# DDR3_2.net
KiCad netlist of a schematic drawn in Altium Designer
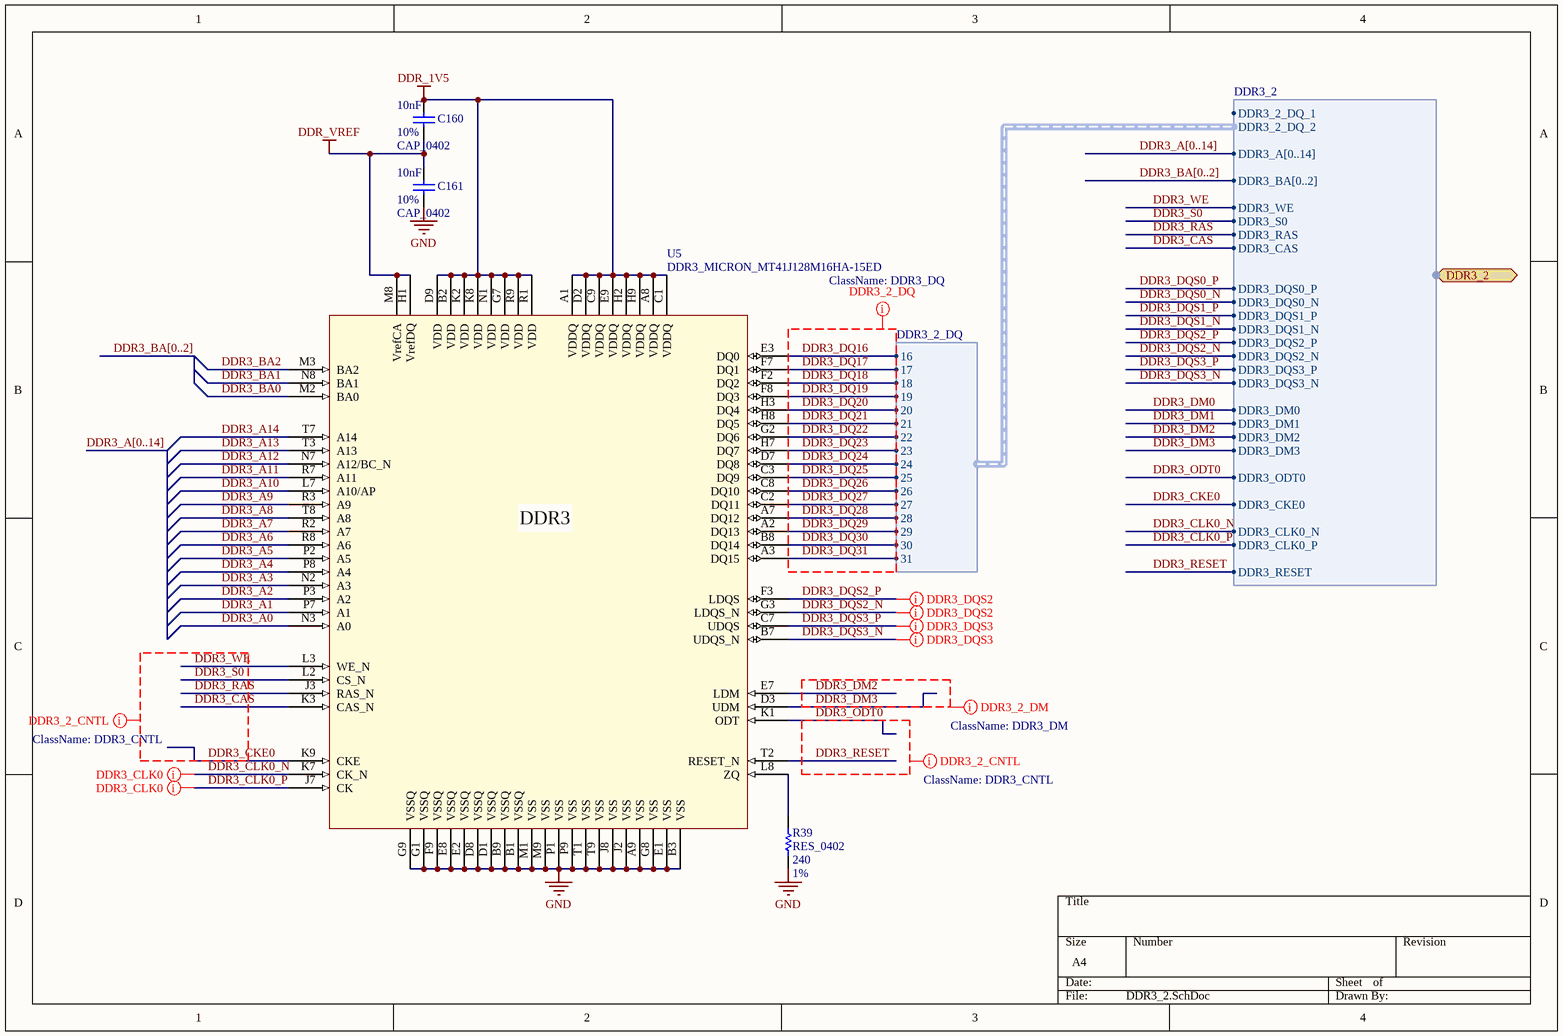
[diagram p0: DDR3_2.SchDoc]

(export (version "E")
  (design (tool "Eeschema 10.0.6"))
  (components
    (comp (ref "C160")
      (value "CAP_0402")
      (footprint "CAPC0402(1005)60_N:CAPC0402(1005)60_N")
      (description "10000pF, ceramic, 10% 6.3V X5R, 0402")
      (fields
        (field (name "ALTIUM_VALUE") "10nF")
        (field (name "TOLERANCE") "10%")
        (field (name "PART NUMBER") "GRM155R60J103KA01D")
        (field (name "MANUFACTURER") "Murata Electronics North America")
      )
      (libsource (lib "COMRAD_Database") (part "CAP_0402"))
    )
    (comp (ref "C161")
      (value "CAP_0402")
      (footprint "CAPC0402(1005)60_N:CAPC0402(1005)60_N")
      (description "10000pF, ceramic, 10% 6.3V X5R, 0402")
      (fields
        (field (name "ALTIUM_VALUE") "10nF")
        (field (name "TOLERANCE") "10%")
        (field (name "PART NUMBER") "GRM155R60J103KA01D")
        (field (name "MANUFACTURER") "Murata Electronics North America")
      )
      (libsource (lib "COMRAD_Database") (part "CAP_0402"))
    )
    (comp (ref "R39")
      (value "RES_0402")
      (footprint "RESC0402(1005)_N:RESC0402(1005)_N")
      (description "240 ohm, 1% 1/16W, 0402")
      (fields
        (field (name "ALTIUM_VALUE") "240")
        (field (name "TOLERANCE") "1%")
        (field (name "PART NUMBER") "CRCW0402240RFKED")
        (field (name "MANUFACTURER") "Vishay/Dale")
      )
      (libsource (lib "COMRAD_Database") (part "RES_0402"))
    )
    (comp (ref "U5")
      (value "DDR3_MICRON_MT41J128M16HA-15ED")
      (footprint "DDR3_MICRON_MT41J128M16HA-15ED_FBGA96")
      (description "MT41J128M16HA-15E:D, DDR3 SDRAM 4Gb x4, x8, x16, FBGA96")
      (fields (field (name "PART NUMBER") "MT41J128M16HA-15E:D TR") (field (name "MANUFACTURER") "MICRON"))
      (libsource (lib "COMRAD_Database") (part "DDR3_MICRON_MT41J128M16HA-15ED"))
    )
  )
  (nets
    (net (code "4") (name "/DDR3_A0") (class "Default")
      (node (ref "U5") (pin "N3") (pinfunction "A0_N3") (pintype "input"))
    )
    (net (code "5") (name "/DDR3_A1") (class "Default")
      (node (ref "U5") (pin "P7") (pinfunction "A1_P7") (pintype "input"))
    )
    (net (code "6") (name "/DDR3_A2") (class "Default")
      (node (ref "U5") (pin "P3") (pinfunction "A2_P3") (pintype "input"))
    )
    (net (code "7") (name "/DDR3_A3") (class "Default")
      (node (ref "U5") (pin "N2") (pinfunction "A3_N2") (pintype "input"))
    )
    (net (code "8") (name "/DDR3_A4") (class "Default")
      (node (ref "U5") (pin "P8") (pinfunction "A4_P8") (pintype "input"))
    )
    (net (code "9") (name "/DDR3_A5") (class "Default")
      (node (ref "U5") (pin "P2") (pinfunction "A5_P2") (pintype "input"))
    )
    (net (code "10") (name "/DDR3_A6") (class "Default")
      (node (ref "U5") (pin "R8") (pinfunction "A6_R8") (pintype "input"))
    )
    (net (code "11") (name "/DDR3_A7") (class "Default")
      (node (ref "U5") (pin "R2") (pinfunction "A7_R2") (pintype "input"))
    )
    (net (code "12") (name "/DDR3_A8") (class "Default")
      (node (ref "U5") (pin "T8") (pinfunction "A8_T8") (pintype "input"))
    )
    (net (code "13") (name "/DDR3_A9") (class "Default")
      (node (ref "U5") (pin "R3") (pinfunction "A9_R3") (pintype "input"))
    )
    (net (code "14") (name "/DDR3_A10") (class "Default")
      (node (ref "U5") (pin "L7") (pinfunction "A10/AP_L7") (pintype "input"))
    )
    (net (code "15") (name "/DDR3_A11") (class "Default")
      (node (ref "U5") (pin "R7") (pinfunction "A11_R7") (pintype "input"))
    )
    (net (code "16") (name "/DDR3_A12") (class "Default")
      (node (ref "U5") (pin "N7") (pinfunction "A12/BC_N_N7") (pintype "input"))
    )
    (net (code "17") (name "/DDR3_A13") (class "Default")
      (node (ref "U5") (pin "T3") (pinfunction "A13_T3") (pintype "input"))
    )
    (net (code "18") (name "/DDR3_A14") (class "Default")
      (node (ref "U5") (pin "T7") (pinfunction "A14_T7") (pintype "input"))
    )
    (net (code "20") (name "/DDR3_BA0") (class "Default")
      (node (ref "U5") (pin "M2") (pinfunction "BA0_M2") (pintype "input"))
    )
    (net (code "21") (name "/DDR3_BA1") (class "Default")
      (node (ref "U5") (pin "N8") (pinfunction "BA1_N8") (pintype "input"))
    )
    (net (code "22") (name "/DDR3_BA2") (class "Default")
      (node (ref "U5") (pin "M3") (pinfunction "BA2_M3") (pintype "input"))
    )
    (net (code "24") (name "/DDR3_CAS") (class "Default")
      (node (ref "U5") (pin "K3") (pinfunction "CAS_N_K3") (pintype "input"))
    )
    (net (code "25") (name "/DDR3_CKE0") (class "Default")
      (node (ref "U5") (pin "K9") (pinfunction "CKE_K9") (pintype "input"))
    )
    (net (code "26") (name "/DDR3_CLK0_N") (class "Default")
      (node (ref "U5") (pin "K7") (pinfunction "CK_N_K7") (pintype "input"))
    )
    (net (code "27") (name "/DDR3_CLK0_P") (class "Default")
      (node (ref "U5") (pin "J7") (pinfunction "CK_J7") (pintype "input"))
    )
    (net (code "30") (name "/DDR3_DM2") (class "Default")
      (node (ref "U5") (pin "E7") (pinfunction "LDM_E7") (pintype "input"))
    )
    (net (code "31") (name "/DDR3_DM3") (class "Default")
      (node (ref "U5") (pin "D3") (pinfunction "UDM_D3") (pintype "input"))
    )
    (net (code "32") (name "/DDR3_DQ16") (class "Default")
      (node (ref "U5") (pin "E3") (pinfunction "DQ0_E3") (pintype "bidirectional"))
    )
    (net (code "33") (name "/DDR3_DQ17") (class "Default")
      (node (ref "U5") (pin "F7") (pinfunction "DQ1_F7") (pintype "bidirectional"))
    )
    (net (code "34") (name "/DDR3_DQ18") (class "Default")
      (node (ref "U5") (pin "F2") (pinfunction "DQ2_F2") (pintype "bidirectional"))
    )
    (net (code "35") (name "/DDR3_DQ19") (class "Default")
      (node (ref "U5") (pin "F8") (pinfunction "DQ3_F8") (pintype "bidirectional"))
    )
    (net (code "36") (name "/DDR3_DQ20") (class "Default")
      (node (ref "U5") (pin "H3") (pinfunction "DQ4_H3") (pintype "bidirectional"))
    )
    (net (code "37") (name "/DDR3_DQ21") (class "Default")
      (node (ref "U5") (pin "H8") (pinfunction "DQ5_H8") (pintype "bidirectional"))
    )
    (net (code "38") (name "/DDR3_DQ22") (class "Default")
      (node (ref "U5") (pin "G2") (pinfunction "DQ6_G2") (pintype "bidirectional"))
    )
    (net (code "39") (name "/DDR3_DQ23") (class "Default")
      (node (ref "U5") (pin "H7") (pinfunction "DQ7_H7") (pintype "bidirectional"))
    )
    (net (code "40") (name "/DDR3_DQ24") (class "Default")
      (node (ref "U5") (pin "D7") (pinfunction "DQ8_D7") (pintype "bidirectional"))
    )
    (net (code "41") (name "/DDR3_DQ25") (class "Default")
      (node (ref "U5") (pin "C3") (pinfunction "DQ9_C3") (pintype "bidirectional"))
    )
    (net (code "42") (name "/DDR3_DQ26") (class "Default")
      (node (ref "U5") (pin "C8") (pinfunction "DQ10_C8") (pintype "bidirectional"))
    )
    (net (code "43") (name "/DDR3_DQ27") (class "Default")
      (node (ref "U5") (pin "C2") (pinfunction "DQ11_C2") (pintype "bidirectional"))
    )
    (net (code "44") (name "/DDR3_DQ28") (class "Default")
      (node (ref "U5") (pin "A7") (pinfunction "DQ12_A7") (pintype "bidirectional"))
    )
    (net (code "45") (name "/DDR3_DQ29") (class "Default")
      (node (ref "U5") (pin "A2") (pinfunction "DQ13_A2") (pintype "bidirectional"))
    )
    (net (code "46") (name "/DDR3_DQ30") (class "Default")
      (node (ref "U5") (pin "B8") (pinfunction "DQ14_B8") (pintype "bidirectional"))
    )
    (net (code "47") (name "/DDR3_DQ31") (class "Default")
      (node (ref "U5") (pin "A3") (pinfunction "DQ15_A3") (pintype "bidirectional"))
    )
    (net (code "52") (name "/DDR3_DQS2_N") (class "Default")
      (node (ref "U5") (pin "G3") (pinfunction "LDQS_N_G3") (pintype "bidirectional"))
    )
    (net (code "53") (name "/DDR3_DQS2_P") (class "Default")
      (node (ref "U5") (pin "F3") (pinfunction "LDQS_F3") (pintype "bidirectional"))
    )
    (net (code "54") (name "/DDR3_DQS3_N") (class "Default")
      (node (ref "U5") (pin "B7") (pinfunction "UDQS_N_B7") (pintype "bidirectional"))
    )
    (net (code "55") (name "/DDR3_DQS3_P") (class "Default")
      (node (ref "U5") (pin "C7") (pinfunction "UDQS_C7") (pintype "bidirectional"))
    )
    (net (code "56") (name "/DDR3_ODT0") (class "Default")
      (node (ref "U5") (pin "K1") (pinfunction "ODT_K1") (pintype "input"))
    )
    (net (code "57") (name "/DDR3_RAS") (class "Default")
      (node (ref "U5") (pin "J3") (pinfunction "RAS_N_J3") (pintype "input"))
    )
    (net (code "58") (name "/DDR3_RESET") (class "Default")
      (node (ref "U5") (pin "T2") (pinfunction "RESET_N_T2") (pintype "input"))
    )
    (net (code "59") (name "/DDR3_S0") (class "Default")
      (node (ref "U5") (pin "L2") (pinfunction "CS_N_L2") (pintype "input"))
    )
    (net (code "60") (name "/DDR3_WE") (class "Default")
      (node (ref "U5") (pin "L3") (pinfunction "WE_N_L3") (pintype "input"))
    )
    (net (code "63") (name "DDR_1V5") (class "Default")
      (node (ref "C160") (pin "2") (pinfunction "2_2") (pintype "passive"))
      (node (ref "U5") (pin "A1") (pinfunction "VDDQ_A1") (pintype "power_in"))
      (node (ref "U5") (pin "A8") (pinfunction "VDDQ_A8") (pintype "power_in"))
      (node (ref "U5") (pin "B2") (pinfunction "VDD_B2") (pintype "power_in"))
      (node (ref "U5") (pin "C1") (pinfunction "VDDQ_C1") (pintype "power_in"))
      (node (ref "U5") (pin "C9") (pinfunction "VDDQ_C9") (pintype "power_in"))
      (node (ref "U5") (pin "D2") (pinfunction "VDDQ_D2") (pintype "power_in"))
      (node (ref "U5") (pin "D9") (pinfunction "VDD_D9") (pintype "power_in"))
      (node (ref "U5") (pin "E9") (pinfunction "VDDQ_E9") (pintype "power_in"))
      (node (ref "U5") (pin "G7") (pinfunction "VDD_G7") (pintype "power_in"))
      (node (ref "U5") (pin "H2") (pinfunction "VDDQ_H2") (pintype "power_in"))
      (node (ref "U5") (pin "H9") (pinfunction "VDDQ_H9") (pintype "power_in"))
      (node (ref "U5") (pin "K2") (pinfunction "VDD_K2") (pintype "power_in"))
      (node (ref "U5") (pin "K8") (pinfunction "VDD_K8") (pintype "power_in"))
      (node (ref "U5") (pin "N1") (pinfunction "VDD_N1") (pintype "power_in"))
      (node (ref "U5") (pin "R1") (pinfunction "VDD_R1") (pintype "power_in"))
      (node (ref "U5") (pin "R9") (pinfunction "VDD_R9") (pintype "power_in"))
    )
    (net (code "64") (name "DDR_VREF") (class "Default")
      (node (ref "C160") (pin "1") (pinfunction "1_1") (pintype "passive"))
      (node (ref "C161") (pin "2") (pinfunction "2_2") (pintype "passive"))
      (node (ref "U5") (pin "H1") (pinfunction "VrefDQ_H1") (pintype "power_in"))
      (node (ref "U5") (pin "M8") (pinfunction "VrefCA_M8") (pintype "power_in"))
    )
    (net (code "65") (name "GND") (class "Default")
      (node (ref "C161") (pin "1") (pinfunction "1_1") (pintype "passive"))
      (node (ref "R39") (pin "1") (pinfunction "1_1") (pintype "passive"))
      (node (ref "U5") (pin "A9") (pinfunction "VSS_A9") (pintype "power_in"))
      (node (ref "U5") (pin "B1") (pinfunction "VSSQ_B1") (pintype "power_in"))
      (node (ref "U5") (pin "B3") (pinfunction "VSS_B3") (pintype "power_in"))
      (node (ref "U5") (pin "B9") (pinfunction "VSSQ_B9") (pintype "power_in"))
      (node (ref "U5") (pin "D1") (pinfunction "VSSQ_D1") (pintype "power_in"))
      (node (ref "U5") (pin "D8") (pinfunction "VSSQ_D8") (pintype "power_in"))
      (node (ref "U5") (pin "E1") (pinfunction "VSS_E1") (pintype "power_in"))
      (node (ref "U5") (pin "E2") (pinfunction "VSSQ_E2") (pintype "power_in"))
      (node (ref "U5") (pin "E8") (pinfunction "VSSQ_E8") (pintype "power_in"))
      (node (ref "U5") (pin "F9") (pinfunction "VSSQ_F9") (pintype "power_in"))
      (node (ref "U5") (pin "G1") (pinfunction "VSSQ_G1") (pintype "power_in"))
      (node (ref "U5") (pin "G8") (pinfunction "VSS_G8") (pintype "power_in"))
      (node (ref "U5") (pin "G9") (pinfunction "VSSQ_G9") (pintype "power_in"))
      (node (ref "U5") (pin "J2") (pinfunction "VSS_J2") (pintype "power_in"))
      (node (ref "U5") (pin "J8") (pinfunction "VSS_J8") (pintype "power_in"))
      (node (ref "U5") (pin "M1") (pinfunction "VSS_M1") (pintype "power_in"))
      (node (ref "U5") (pin "M9") (pinfunction "VSS_M9") (pintype "power_in"))
      (node (ref "U5") (pin "P1") (pinfunction "VSS_P1") (pintype "power_in"))
      (node (ref "U5") (pin "P9") (pinfunction "VSS_P9") (pintype "power_in"))
      (node (ref "U5") (pin "T1") (pinfunction "VSS_T1") (pintype "power_in"))
      (node (ref "U5") (pin "T9") (pinfunction "VSS_T9") (pintype "power_in"))
    )
    (net (code "66") (name "Net-(U5-ZQ)") (class "Default")
      (node (ref "R39") (pin "2") (pinfunction "2_2") (pintype "passive"))
      (node (ref "U5") (pin "L8") (pinfunction "ZQ_L8") (pintype "input"))
    )
  )
)
